# SuperPET_OS9_MMU_v2_9.net
KiCad netlist of a schematic drawn in EAGLE
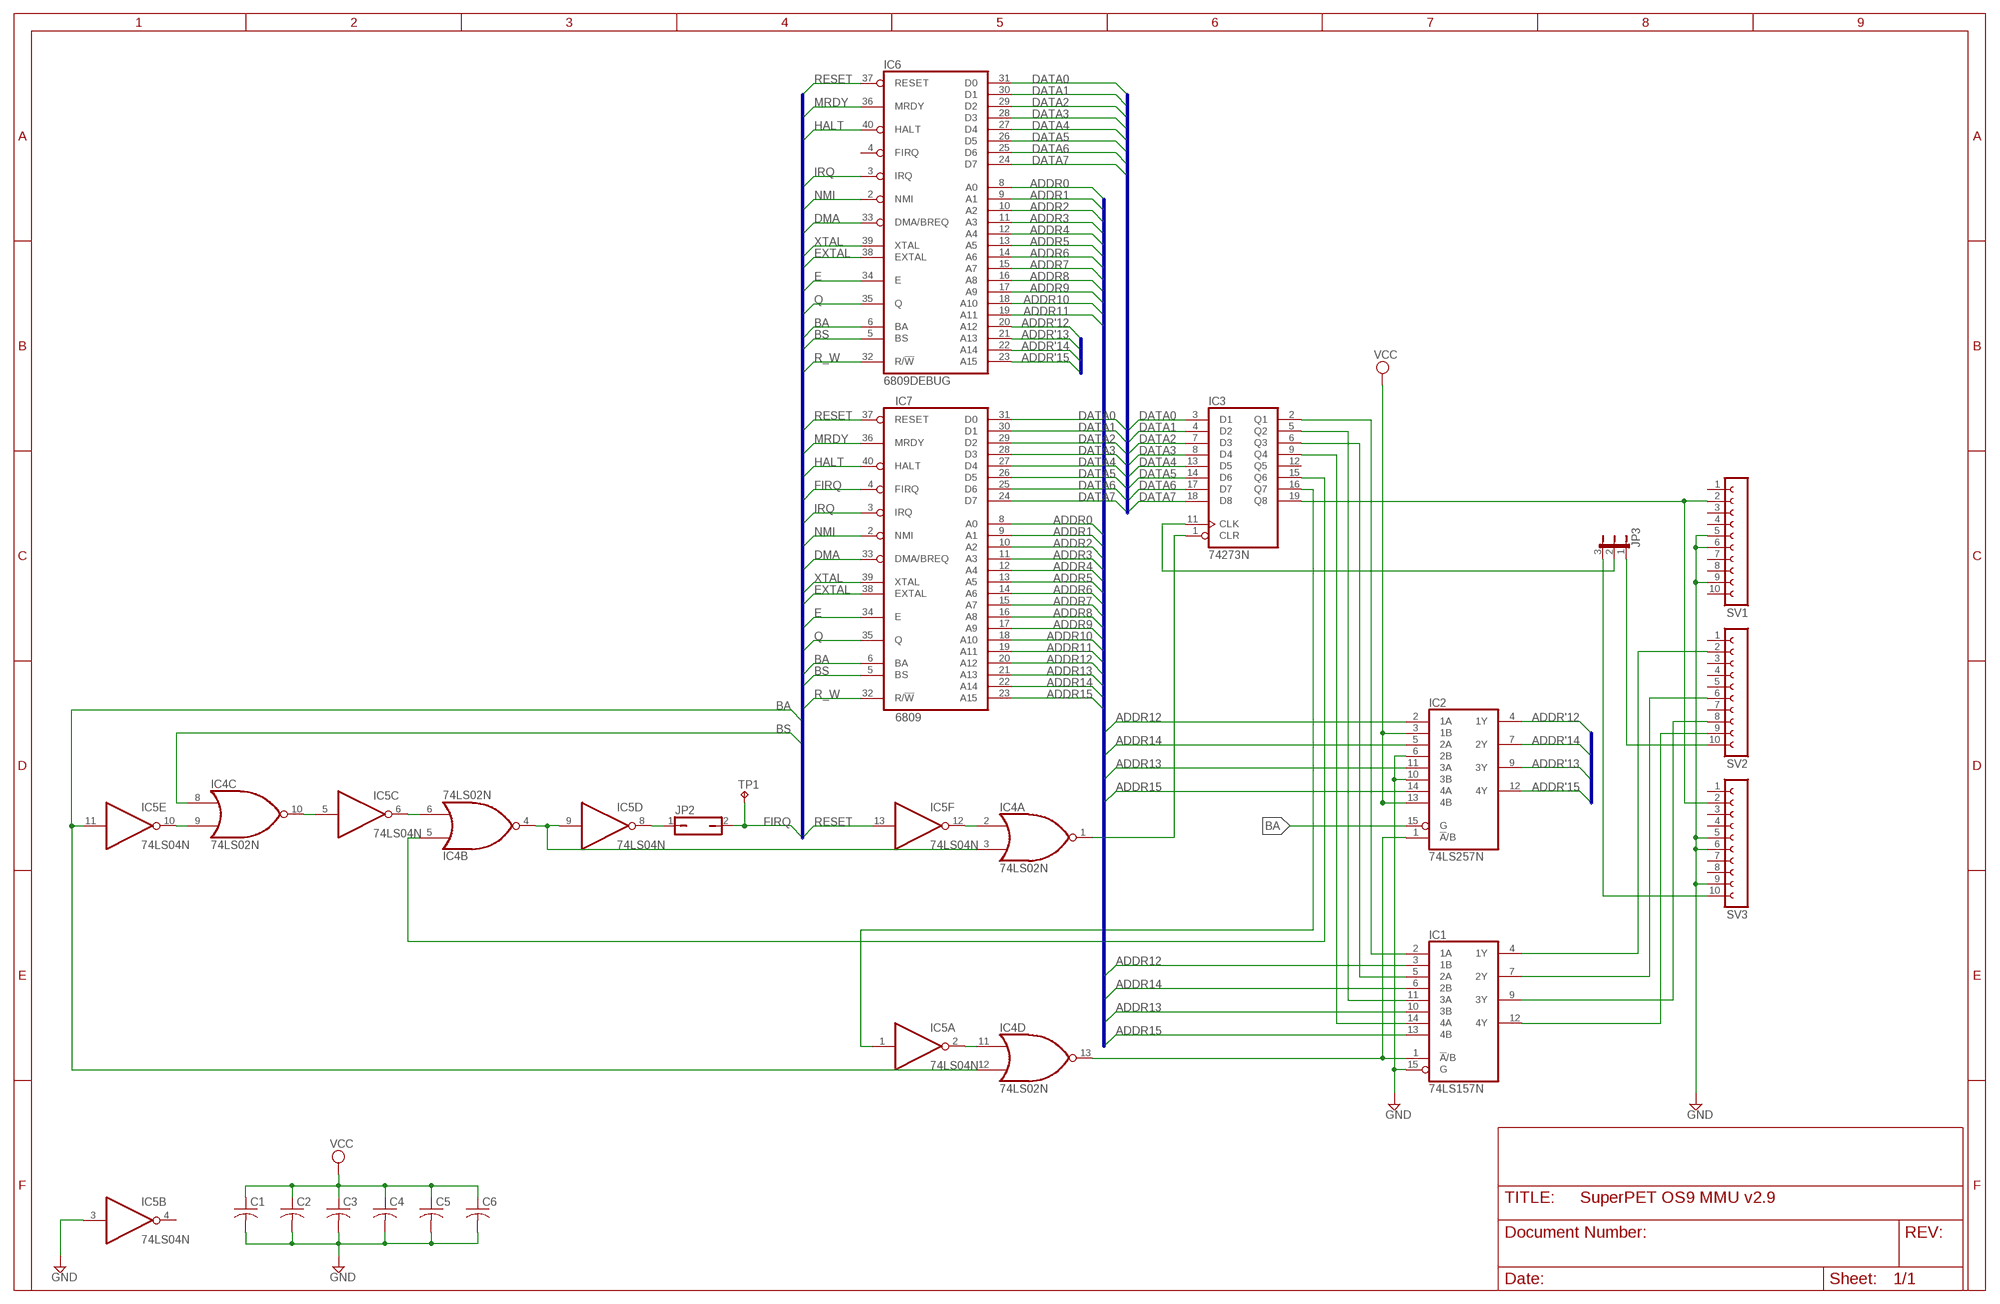
[diagram p0: schematic, sheet 1]

(export (version "E")
  (design (tool "Eeschema 10.0.6"))
  (components
    (comp (ref "C1")
      (value "C-US025-025X050")
      (footprint "eagle-import:C025-025X050")
      (libsource (lib "eagle-import") (part "C-US025-025X050"))
    )
    (comp (ref "C2")
      (value "C-US025-025X050")
      (footprint "eagle-import:C025-025X050")
      (libsource (lib "eagle-import") (part "C-US025-025X050"))
    )
    (comp (ref "C3")
      (value "C-US025-025X050")
      (footprint "eagle-import:C025-025X050")
      (libsource (lib "eagle-import") (part "C-US025-025X050"))
    )
    (comp (ref "C4")
      (value "C-US025-025X050")
      (footprint "eagle-import:C025-025X050")
      (libsource (lib "eagle-import") (part "C-US025-025X050"))
    )
    (comp (ref "C5")
      (value "C-US025-025X050")
      (footprint "eagle-import:C025-025X050")
      (libsource (lib "eagle-import") (part "C-US025-025X050"))
    )
    (comp (ref "C6")
      (value "C-US025-025X050")
      (footprint "eagle-import:C025-025X050")
      (libsource (lib "eagle-import") (part "C-US025-025X050"))
    )
    (comp (ref "IC1")
      (value "74LS157N")
      (footprint "eagle-import:DIL16")
      (libsource (lib "eagle-import") (part "74157NLS"))
    )
    (comp (ref "IC2")
      (value "74LS257N")
      (footprint "eagle-import:DIL16")
      (libsource (lib "eagle-import") (part "74257NLS"))
    )
    (comp (ref "IC3")
      (value "74273N")
      (footprint "eagle-import:DIL20")
      (libsource (lib "eagle-import") (part "74273N"))
    )
    (comp (ref "IC4")
      (value "74LS02N")
      (footprint "eagle-import:DIL14")
      (libsource (lib "eagle-import") (part "7402NLS"))
    )
    (comp (ref "IC5")
      (value "74LS04N")
      (footprint "eagle-import:DIL14")
      (libsource (lib "eagle-import") (part "7404NLS"))
    )
    (comp (ref "IC6")
      (value "6809DEBUG")
      (footprint "eagle-import:DIL40")
      (libsource (lib "eagle-import") (part "6809DEBUG"))
    )
    (comp (ref "IC7")
      (value "6809")
      (footprint "eagle-import:DIL40")
      (libsource (lib "eagle-import") (part "6809"))
    )
    (comp (ref "JP2")
      (value "JP1Q")
      (footprint "eagle-import:JP1")
      (libsource (lib "eagle-import") (part "JP1Q"))
    )
    (comp (ref "JP3")
      (value "JP2E")
      (footprint "eagle-import:JP2")
      (libsource (lib "eagle-import") (part "JP2E"))
    )
    (comp (ref "SV1")
      (value "FE10-1")
      (footprint "eagle-import:FE10")
      (libsource (lib "eagle-import") (part "FE10-1"))
    )
    (comp (ref "SV2")
      (value "FE10-1")
      (footprint "eagle-import:FE10")
      (libsource (lib "eagle-import") (part "FE10-1"))
    )
    (comp (ref "SV3")
      (value "FE10-1")
      (footprint "eagle-import:FE10")
      (libsource (lib "eagle-import") (part "FE10-1"))
    )
    (comp (ref "TP1")
      (value "TPPAD1-17")
      (footprint "eagle-import:P1-17")
      (libsource (lib "eagle-import") (part "TPPAD1-17"))
    )
  )
  (nets
    (net (code "1") (name "/ADDR'12") (class "Default")
      (node (ref "IC2") (pin "4") (pinfunction "1Y_4") (pintype "tri_state"))
      (node (ref "IC6") (pin "20") (pinfunction "A12_20") (pintype "tri_state"))
    )
    (net (code "2") (name "/ADDR'13") (class "Default")
      (node (ref "IC2") (pin "9") (pinfunction "3Y_9") (pintype "tri_state"))
      (node (ref "IC6") (pin "21") (pinfunction "A13_21") (pintype "tri_state"))
    )
    (net (code "3") (name "/ADDR'14") (class "Default")
      (node (ref "IC2") (pin "7") (pinfunction "2Y_7") (pintype "tri_state"))
      (node (ref "IC6") (pin "22") (pinfunction "A14_22") (pintype "tri_state"))
    )
    (net (code "4") (name "/ADDR'15") (class "Default")
      (node (ref "IC2") (pin "12") (pinfunction "4Y_12") (pintype "tri_state"))
      (node (ref "IC6") (pin "23") (pinfunction "A15_23") (pintype "tri_state"))
    )
    (net (code "5") (name "/ADDR0") (class "Default")
      (node (ref "IC6") (pin "8") (pinfunction "A0_8") (pintype "tri_state"))
      (node (ref "IC7") (pin "8") (pinfunction "A0_8") (pintype "tri_state"))
    )
    (net (code "6") (name "/ADDR1") (class "Default")
      (node (ref "IC6") (pin "9") (pinfunction "A1_9") (pintype "tri_state"))
      (node (ref "IC7") (pin "9") (pinfunction "A1_9") (pintype "tri_state"))
    )
    (net (code "7") (name "/ADDR2") (class "Default")
      (node (ref "IC6") (pin "10") (pinfunction "A2_10") (pintype "tri_state"))
      (node (ref "IC7") (pin "10") (pinfunction "A2_10") (pintype "tri_state"))
    )
    (net (code "8") (name "/ADDR3") (class "Default")
      (node (ref "IC6") (pin "11") (pinfunction "A3_11") (pintype "tri_state"))
      (node (ref "IC7") (pin "11") (pinfunction "A3_11") (pintype "tri_state"))
    )
    (net (code "9") (name "/ADDR4") (class "Default")
      (node (ref "IC6") (pin "12") (pinfunction "A4_12") (pintype "tri_state"))
      (node (ref "IC7") (pin "12") (pinfunction "A4_12") (pintype "tri_state"))
    )
    (net (code "10") (name "/ADDR5") (class "Default")
      (node (ref "IC6") (pin "13") (pinfunction "A5_13") (pintype "tri_state"))
      (node (ref "IC7") (pin "13") (pinfunction "A5_13") (pintype "tri_state"))
    )
    (net (code "11") (name "/ADDR6") (class "Default")
      (node (ref "IC6") (pin "14") (pinfunction "A6_14") (pintype "tri_state"))
      (node (ref "IC7") (pin "14") (pinfunction "A6_14") (pintype "tri_state"))
    )
    (net (code "12") (name "/ADDR7") (class "Default")
      (node (ref "IC6") (pin "15") (pinfunction "A7_15") (pintype "tri_state"))
      (node (ref "IC7") (pin "15") (pinfunction "A7_15") (pintype "tri_state"))
    )
    (net (code "13") (name "/ADDR8") (class "Default")
      (node (ref "IC6") (pin "16") (pinfunction "A8_16") (pintype "tri_state"))
      (node (ref "IC7") (pin "16") (pinfunction "A8_16") (pintype "tri_state"))
    )
    (net (code "14") (name "/ADDR9") (class "Default")
      (node (ref "IC6") (pin "17") (pinfunction "A9_17") (pintype "tri_state"))
      (node (ref "IC7") (pin "17") (pinfunction "A9_17") (pintype "tri_state"))
    )
    (net (code "15") (name "/ADDR10") (class "Default")
      (node (ref "IC6") (pin "18") (pinfunction "A10_18") (pintype "tri_state"))
      (node (ref "IC7") (pin "18") (pinfunction "A10_18") (pintype "tri_state"))
    )
    (net (code "16") (name "/ADDR11") (class "Default")
      (node (ref "IC6") (pin "19") (pinfunction "A11_19") (pintype "tri_state"))
      (node (ref "IC7") (pin "19") (pinfunction "A11_19") (pintype "tri_state"))
    )
    (net (code "17") (name "/ADDR12") (class "Default")
      (node (ref "IC1") (pin "3") (pinfunction "1B_3") (pintype "input"))
      (node (ref "IC2") (pin "2") (pinfunction "1A_2") (pintype "input"))
      (node (ref "IC7") (pin "20") (pinfunction "A12_20") (pintype "tri_state"))
    )
    (net (code "18") (name "/ADDR13") (class "Default")
      (node (ref "IC1") (pin "10") (pinfunction "3B_10") (pintype "input"))
      (node (ref "IC2") (pin "11") (pinfunction "3A_11") (pintype "input"))
      (node (ref "IC7") (pin "21") (pinfunction "A13_21") (pintype "tri_state"))
    )
    (net (code "19") (name "/ADDR14") (class "Default")
      (node (ref "IC1") (pin "6") (pinfunction "2B_6") (pintype "input"))
      (node (ref "IC2") (pin "5") (pinfunction "2A_5") (pintype "input"))
      (node (ref "IC7") (pin "22") (pinfunction "A14_22") (pintype "tri_state"))
    )
    (net (code "20") (name "/ADDR15") (class "Default")
      (node (ref "IC1") (pin "13") (pinfunction "4B_13") (pintype "input"))
      (node (ref "IC2") (pin "14") (pinfunction "4A_14") (pintype "input"))
      (node (ref "IC7") (pin "23") (pinfunction "A15_23") (pintype "tri_state"))
    )
    (net (code "21") (name "/BS") (class "Default")
      (node (ref "IC4") (pin "8") (pinfunction "I0_8") (pintype "input"))
      (node (ref "IC6") (pin "5") (pinfunction "BS_5") (pintype "input"))
      (node (ref "IC7") (pin "5") (pinfunction "BS_5") (pintype "output"))
    )
    (net (code "22") (name "/DATA0") (class "Default")
      (node (ref "IC3") (pin "3") (pinfunction "D1_3") (pintype "input"))
      (node (ref "IC6") (pin "31") (pinfunction "D0_31") (pintype "bidirectional"))
      (node (ref "IC7") (pin "31") (pinfunction "D0_31") (pintype "bidirectional"))
    )
    (net (code "23") (name "/DATA1") (class "Default")
      (node (ref "IC3") (pin "4") (pinfunction "D2_4") (pintype "input"))
      (node (ref "IC6") (pin "30") (pinfunction "D1_30") (pintype "bidirectional"))
      (node (ref "IC7") (pin "30") (pinfunction "D1_30") (pintype "bidirectional"))
    )
    (net (code "24") (name "/DATA2") (class "Default")
      (node (ref "IC3") (pin "7") (pinfunction "D3_7") (pintype "input"))
      (node (ref "IC6") (pin "29") (pinfunction "D2_29") (pintype "bidirectional"))
      (node (ref "IC7") (pin "29") (pinfunction "D2_29") (pintype "bidirectional"))
    )
    (net (code "25") (name "/DATA3") (class "Default")
      (node (ref "IC3") (pin "8") (pinfunction "D4_8") (pintype "input"))
      (node (ref "IC6") (pin "28") (pinfunction "D3_28") (pintype "bidirectional"))
      (node (ref "IC7") (pin "28") (pinfunction "D3_28") (pintype "bidirectional"))
    )
    (net (code "26") (name "/DATA4") (class "Default")
      (node (ref "IC3") (pin "13") (pinfunction "D5_13") (pintype "input"))
      (node (ref "IC6") (pin "27") (pinfunction "D4_27") (pintype "bidirectional"))
      (node (ref "IC7") (pin "27") (pinfunction "D4_27") (pintype "bidirectional"))
    )
    (net (code "27") (name "/DATA5") (class "Default")
      (node (ref "IC3") (pin "14") (pinfunction "D6_14") (pintype "input"))
      (node (ref "IC6") (pin "26") (pinfunction "D5_26") (pintype "bidirectional"))
      (node (ref "IC7") (pin "26") (pinfunction "D5_26") (pintype "bidirectional"))
    )
    (net (code "28") (name "/DATA6") (class "Default")
      (node (ref "IC3") (pin "17") (pinfunction "D7_17") (pintype "input"))
      (node (ref "IC6") (pin "25") (pinfunction "D6_25") (pintype "bidirectional"))
      (node (ref "IC7") (pin "25") (pinfunction "D6_25") (pintype "bidirectional"))
    )
    (net (code "29") (name "/DATA7") (class "Default")
      (node (ref "IC3") (pin "18") (pinfunction "D8_18") (pintype "input"))
      (node (ref "IC6") (pin "24") (pinfunction "D7_24") (pintype "bidirectional"))
      (node (ref "IC7") (pin "24") (pinfunction "D7_24") (pintype "bidirectional"))
    )
    (net (code "30") (name "/DMA") (class "Default")
      (node (ref "IC6") (pin "33") (pinfunction "DMA/BREQ_33") (pintype "output"))
      (node (ref "IC7") (pin "33") (pinfunction "DMA/BREQ_33") (pintype "input"))
    )
    (net (code "31") (name "/E") (class "Default")
      (node (ref "IC6") (pin "34") (pinfunction "E_34") (pintype "input"))
      (node (ref "IC7") (pin "34") (pinfunction "E_34") (pintype "output"))
    )
    (net (code "32") (name "/EXTAL") (class "Default")
      (node (ref "IC6") (pin "38") (pinfunction "EXTAL_38") (pintype "output"))
      (node (ref "IC7") (pin "38") (pinfunction "EXTAL_38") (pintype "input"))
    )
    (net (code "33") (name "/FIRQ") (class "Default")
      (node (ref "IC7") (pin "4") (pinfunction "FIRQ_4") (pintype "input"))
      (node (ref "JP2") (pin "2") (pinfunction "2_2") (pintype "passive"))
      (node (ref "TP1") (pin "1") (pinfunction "TP_1") (pintype "input"))
    )
    (net (code "34") (name "/HALT") (class "Default")
      (node (ref "IC6") (pin "40") (pinfunction "HALT_40") (pintype "output"))
      (node (ref "IC7") (pin "40") (pinfunction "HALT_40") (pintype "input"))
    )
    (net (code "35") (name "/IRQ") (class "Default")
      (node (ref "IC6") (pin "3") (pinfunction "IRQ_3") (pintype "output"))
      (node (ref "IC7") (pin "3") (pinfunction "IRQ_3") (pintype "input"))
    )
    (net (code "36") (name "/MRDY") (class "Default")
      (node (ref "IC6") (pin "36") (pinfunction "MRDY_36") (pintype "output"))
      (node (ref "IC7") (pin "36") (pinfunction "MRDY_36") (pintype "input"))
    )
    (net (code "37") (name "/NMI") (class "Default")
      (node (ref "IC6") (pin "2") (pinfunction "NMI_2") (pintype "output"))
      (node (ref "IC7") (pin "2") (pinfunction "NMI_2") (pintype "input"))
    )
    (net (code "38") (name "/Q") (class "Default")
      (node (ref "IC6") (pin "35") (pinfunction "Q_35") (pintype "input"))
      (node (ref "IC7") (pin "35") (pinfunction "Q_35") (pintype "output"))
    )
    (net (code "39") (name "/RESET") (class "Default")
      (node (ref "IC5") (pin "13") (pinfunction "I_13") (pintype "input"))
      (node (ref "IC6") (pin "37") (pinfunction "RESET_37") (pintype "output"))
      (node (ref "IC7") (pin "37") (pinfunction "RESET_37") (pintype "input"))
    )
    (net (code "40") (name "/R_W") (class "Default")
      (node (ref "IC6") (pin "32") (pinfunction "R/~{W}_32") (pintype "input"))
      (node (ref "IC7") (pin "32") (pinfunction "R/~{W}_32") (pintype "output"))
    )
    (net (code "41") (name "/XTAL") (class "Default")
      (node (ref "IC6") (pin "39") (pinfunction "XTAL_39") (pintype "output"))
      (node (ref "IC7") (pin "39") (pinfunction "XTAL_39") (pintype "input"))
    )
    (net (code "42") (name "BA") (class "Default")
      (node (ref "IC2") (pin "15") (pinfunction "G_15") (pintype "input"))
      (node (ref "IC4") (pin "12") (pinfunction "I1_12") (pintype "input"))
      (node (ref "IC5") (pin "11") (pinfunction "I_11") (pintype "input"))
      (node (ref "IC6") (pin "6") (pinfunction "BA_6") (pintype "input"))
      (node (ref "IC7") (pin "6") (pinfunction "BA_6") (pintype "output"))
    )
    (net (code "43") (name "GND") (class "Default")
      (node (ref "C1") (pin "2") (pinfunction "2_2") (pintype "passive"))
      (node (ref "C2") (pin "2") (pinfunction "2_2") (pintype "passive"))
      (node (ref "C3") (pin "2") (pinfunction "2_2") (pintype "passive"))
      (node (ref "C4") (pin "2") (pinfunction "2_2") (pintype "passive"))
      (node (ref "C5") (pin "2") (pinfunction "2_2") (pintype "passive"))
      (node (ref "C6") (pin "2") (pinfunction "2_2") (pintype "passive"))
      (node (ref "IC1") (pin "15") (pinfunction "G_15") (pintype "input"))
      (node (ref "IC2") (pin "10") (pinfunction "3B_10") (pintype "input"))
      (node (ref "IC2") (pin "6") (pinfunction "2B_6") (pintype "input"))
      (node (ref "IC5") (pin "3") (pinfunction "I_3") (pintype "input"))
      (node (ref "SV1") (pin "5") (pinfunction "5_5") (pintype "passive"))
      (node (ref "SV1") (pin "6") (pinfunction "6_6") (pintype "passive"))
      (node (ref "SV1") (pin "9") (pinfunction "9_9") (pintype "passive"))
      (node (ref "SV3") (pin "5") (pinfunction "5_5") (pintype "passive"))
      (node (ref "SV3") (pin "6") (pinfunction "6_6") (pintype "passive"))
      (node (ref "SV3") (pin "9") (pinfunction "9_9") (pintype "passive"))
    )
    (net (code "44") (name "Net-(IC1A-1A)") (class "Default")
      (node (ref "IC1") (pin "2") (pinfunction "1A_2") (pintype "input"))
      (node (ref "IC3") (pin "2") (pinfunction "Q1_2") (pintype "output"))
    )
    (net (code "45") (name "Net-(IC1A-1Y)") (class "Default")
      (node (ref "IC1") (pin "4") (pinfunction "1Y_4") (pintype "output"))
      (node (ref "SV2") (pin "2") (pinfunction "2_2") (pintype "passive"))
    )
    (net (code "46") (name "Net-(IC1A-2A)") (class "Default")
      (node (ref "IC1") (pin "5") (pinfunction "2A_5") (pintype "input"))
      (node (ref "IC3") (pin "6") (pinfunction "Q3_6") (pintype "output"))
    )
    (net (code "47") (name "Net-(IC1A-2Y)") (class "Default")
      (node (ref "IC1") (pin "7") (pinfunction "2Y_7") (pintype "output"))
      (node (ref "SV2") (pin "6") (pinfunction "6_6") (pintype "passive"))
    )
    (net (code "48") (name "Net-(IC1A-3A)") (class "Default")
      (node (ref "IC1") (pin "11") (pinfunction "3A_11") (pintype "input"))
      (node (ref "IC3") (pin "5") (pinfunction "Q2_5") (pintype "output"))
    )
    (net (code "49") (name "Net-(IC1A-3Y)") (class "Default")
      (node (ref "IC1") (pin "9") (pinfunction "3Y_9") (pintype "output"))
      (node (ref "SV2") (pin "8") (pinfunction "8_8") (pintype "passive"))
    )
    (net (code "50") (name "Net-(IC1A-4A)") (class "Default")
      (node (ref "IC1") (pin "14") (pinfunction "4A_14") (pintype "input"))
      (node (ref "IC3") (pin "9") (pinfunction "Q4_9") (pintype "output"))
    )
    (net (code "51") (name "Net-(IC1A-4Y)") (class "Default")
      (node (ref "IC1") (pin "12") (pinfunction "4Y_12") (pintype "output"))
      (node (ref "SV2") (pin "9") (pinfunction "9_9") (pintype "passive"))
    )
    (net (code "52") (name "Net-(IC1A-~{A}{slash}B)") (class "Default")
      (node (ref "IC1") (pin "1") (pinfunction "~{A}/B_1") (pintype "input"))
      (node (ref "IC2") (pin "1") (pinfunction "~{A}/B_1") (pintype "input"))
      (node (ref "IC4") (pin "13") (pinfunction "O_13") (pintype "output"))
    )
    (net (code "53") (name "Net-(IC3A-CLK)") (class "Default")
      (node (ref "IC3") (pin "11") (pinfunction "CLK_11") (pintype "input"))
      (node (ref "JP3") (pin "2") (pinfunction "2_2") (pintype "passive"))
    )
    (net (code "54") (name "Net-(IC3A-CLR)") (class "Default")
      (node (ref "IC3") (pin "1") (pinfunction "CLR_1") (pintype "input"))
      (node (ref "IC4") (pin "1") (pinfunction "O_1") (pintype "output"))
    )
    (net (code "55") (name "Net-(IC3A-Q6)") (class "Default")
      (node (ref "IC3") (pin "15") (pinfunction "Q6_15") (pintype "output"))
      (node (ref "IC4") (pin "5") (pinfunction "I0_5") (pintype "input"))
    )
    (net (code "56") (name "Net-(IC3A-Q7)") (class "Default")
      (node (ref "IC3") (pin "16") (pinfunction "Q7_16") (pintype "output"))
      (node (ref "IC5") (pin "1") (pinfunction "I_1") (pintype "input"))
    )
    (net (code "57") (name "Net-(IC3A-Q8)") (class "Default")
      (node (ref "IC3") (pin "19") (pinfunction "Q8_19") (pintype "output"))
      (node (ref "SV1") (pin "2") (pinfunction "2_2") (pintype "passive"))
      (node (ref "SV3") (pin "2") (pinfunction "2_2") (pintype "passive"))
    )
    (net (code "58") (name "Net-(IC4A-I0)") (class "Default")
      (node (ref "IC4") (pin "2") (pinfunction "I0_2") (pintype "input"))
      (node (ref "IC5") (pin "12") (pinfunction "O_12") (pintype "output"))
    )
    (net (code "59") (name "Net-(IC4A-I1)") (class "Default")
      (node (ref "IC4") (pin "3") (pinfunction "I1_3") (pintype "input"))
      (node (ref "IC4") (pin "4") (pinfunction "O_4") (pintype "output"))
      (node (ref "IC5") (pin "9") (pinfunction "I_9") (pintype "input"))
    )
    (net (code "60") (name "Net-(IC4B-I1)") (class "Default")
      (node (ref "IC4") (pin "6") (pinfunction "I1_6") (pintype "input"))
      (node (ref "IC5") (pin "6") (pinfunction "O_6") (pintype "output"))
    )
    (net (code "61") (name "Net-(IC4C-I1)") (class "Default")
      (node (ref "IC4") (pin "9") (pinfunction "I1_9") (pintype "input"))
      (node (ref "IC5") (pin "10") (pinfunction "O_10") (pintype "output"))
    )
    (net (code "62") (name "Net-(IC4C-O)") (class "Default")
      (node (ref "IC4") (pin "10") (pinfunction "O_10") (pintype "output"))
      (node (ref "IC5") (pin "5") (pinfunction "I_5") (pintype "input"))
    )
    (net (code "63") (name "Net-(IC4D-I0)") (class "Default")
      (node (ref "IC4") (pin "11") (pinfunction "I0_11") (pintype "input"))
      (node (ref "IC5") (pin "2") (pinfunction "O_2") (pintype "output"))
    )
    (net (code "64") (name "Net-(IC5D-O)") (class "Default")
      (node (ref "IC5") (pin "8") (pinfunction "O_8") (pintype "output"))
      (node (ref "JP2") (pin "1") (pinfunction "1_1") (pintype "passive"))
    )
    (net (code "65") (name "Net-(JP3-Pad1)") (class "Default")
      (node (ref "JP3") (pin "1") (pinfunction "1_1") (pintype "passive"))
      (node (ref "SV2") (pin "10") (pinfunction "10_10") (pintype "passive"))
    )
    (net (code "66") (name "Net-(JP3-Pad3)") (class "Default")
      (node (ref "JP3") (pin "3") (pinfunction "3_3") (pintype "passive"))
      (node (ref "SV3") (pin "10") (pinfunction "10_10") (pintype "passive"))
    )
    (net (code "67") (name "VCC") (class "Default")
      (node (ref "C1") (pin "1") (pinfunction "1_1") (pintype "passive"))
      (node (ref "C2") (pin "1") (pinfunction "1_1") (pintype "passive"))
      (node (ref "C3") (pin "1") (pinfunction "1_1") (pintype "passive"))
      (node (ref "C4") (pin "1") (pinfunction "1_1") (pintype "passive"))
      (node (ref "C5") (pin "1") (pinfunction "1_1") (pintype "passive"))
      (node (ref "C6") (pin "1") (pinfunction "1_1") (pintype "passive"))
      (node (ref "IC2") (pin "13") (pinfunction "4B_13") (pintype "input"))
      (node (ref "IC2") (pin "3") (pinfunction "1B_3") (pintype "input"))
    )
    (net (code "68") (name "unconnected-(IC3A-Q5-Pad12)") (class "Default")
      (node (ref "IC3") (pin "12") (pinfunction "Q5_12") (pintype "output"))
    )
    (net (code "69") (name "unconnected-(IC5B-O-Pad4)") (class "Default")
      (node (ref "IC5") (pin "4") (pinfunction "O_4") (pintype "output"))
    )
    (net (code "70") (name "unconnected-(IC6A-FIRQ-Pad4)") (class "Default")
      (node (ref "IC6") (pin "4") (pinfunction "FIRQ_4") (pintype "output"))
    )
    (net (code "71") (name "unconnected-(SV1-Pad1)") (class "Default")
      (node (ref "SV1") (pin "1") (pinfunction "1_1") (pintype "passive"))
    )
    (net (code "72") (name "unconnected-(SV1-Pad3)") (class "Default")
      (node (ref "SV1") (pin "3") (pinfunction "3_3") (pintype "passive"))
    )
    (net (code "73") (name "unconnected-(SV1-Pad4)") (class "Default")
      (node (ref "SV1") (pin "4") (pinfunction "4_4") (pintype "passive"))
    )
    (net (code "74") (name "unconnected-(SV1-Pad7)") (class "Default")
      (node (ref "SV1") (pin "7") (pinfunction "7_7") (pintype "passive"))
    )
    (net (code "75") (name "unconnected-(SV1-Pad8)") (class "Default")
      (node (ref "SV1") (pin "8") (pinfunction "8_8") (pintype "passive"))
    )
    (net (code "76") (name "unconnected-(SV1-Pad10)") (class "Default")
      (node (ref "SV1") (pin "10") (pinfunction "10_10") (pintype "passive"))
    )
    (net (code "77") (name "unconnected-(SV2-Pad1)") (class "Default")
      (node (ref "SV2") (pin "1") (pinfunction "1_1") (pintype "passive"))
    )
    (net (code "78") (name "unconnected-(SV2-Pad3)") (class "Default")
      (node (ref "SV2") (pin "3") (pinfunction "3_3") (pintype "passive"))
    )
    (net (code "79") (name "unconnected-(SV2-Pad4)") (class "Default")
      (node (ref "SV2") (pin "4") (pinfunction "4_4") (pintype "passive"))
    )
    (net (code "80") (name "unconnected-(SV2-Pad5)") (class "Default")
      (node (ref "SV2") (pin "5") (pinfunction "5_5") (pintype "passive"))
    )
    (net (code "81") (name "unconnected-(SV2-Pad7)") (class "Default")
      (node (ref "SV2") (pin "7") (pinfunction "7_7") (pintype "passive"))
    )
    (net (code "82") (name "unconnected-(SV3-Pad1)") (class "Default")
      (node (ref "SV3") (pin "1") (pinfunction "1_1") (pintype "passive"))
    )
    (net (code "83") (name "unconnected-(SV3-Pad3)") (class "Default")
      (node (ref "SV3") (pin "3") (pinfunction "3_3") (pintype "passive"))
    )
    (net (code "84") (name "unconnected-(SV3-Pad4)") (class "Default")
      (node (ref "SV3") (pin "4") (pinfunction "4_4") (pintype "passive"))
    )
    (net (code "85") (name "unconnected-(SV3-Pad7)") (class "Default")
      (node (ref "SV3") (pin "7") (pinfunction "7_7") (pintype "passive"))
    )
    (net (code "86") (name "unconnected-(SV3-Pad8)") (class "Default")
      (node (ref "SV3") (pin "8") (pinfunction "8_8") (pintype "passive"))
    )
  )
)
